# led-cube.net
KiCad netlist of a schematic drawn in EAGLE
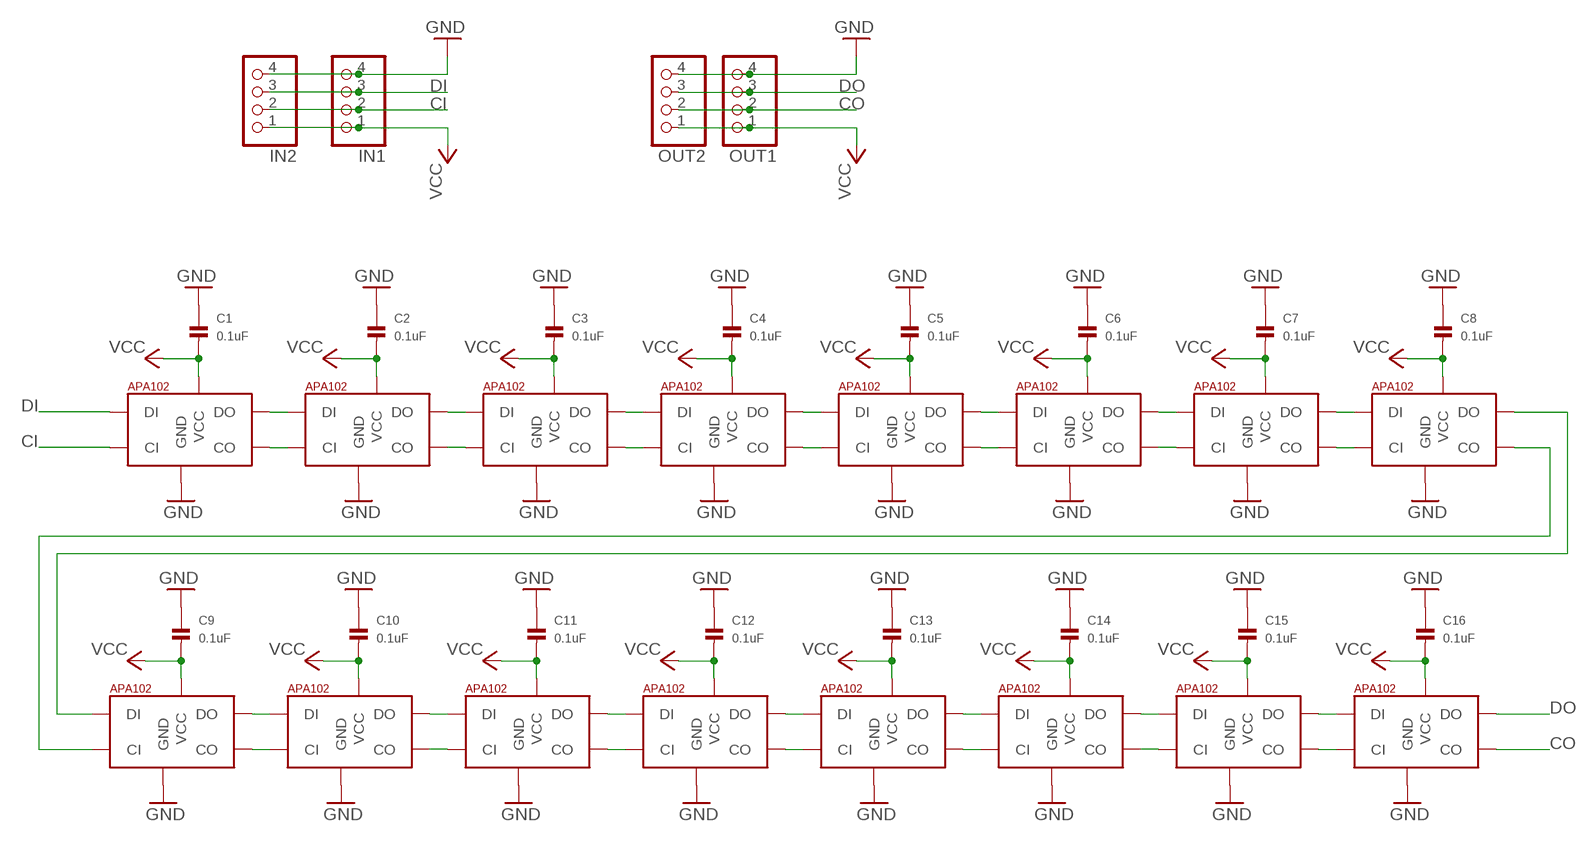
[diagram p0: schematic, sheet 1]

(export (version "E")
  (design (tool "Eeschema 10.0.6"))
  (components
    (comp (ref "C1")
      (value "0.1uF")
      (footprint "eagle-import:0603")
      (libsource (lib "eagle-import") (part "CAP_CERAMIC0603"))
    )
    (comp (ref "C2")
      (value "0.1uF")
      (footprint "eagle-import:0603")
      (libsource (lib "eagle-import") (part "CAP_CERAMIC0603"))
    )
    (comp (ref "C3")
      (value "0.1uF")
      (footprint "eagle-import:0603")
      (libsource (lib "eagle-import") (part "CAP_CERAMIC0603"))
    )
    (comp (ref "C4")
      (value "0.1uF")
      (footprint "eagle-import:0603")
      (libsource (lib "eagle-import") (part "CAP_CERAMIC0603"))
    )
    (comp (ref "C5")
      (value "0.1uF")
      (footprint "eagle-import:0603")
      (libsource (lib "eagle-import") (part "CAP_CERAMIC0603"))
    )
    (comp (ref "C6")
      (value "0.1uF")
      (footprint "eagle-import:0603")
      (libsource (lib "eagle-import") (part "CAP_CERAMIC0603"))
    )
    (comp (ref "C7")
      (value "0.1uF")
      (footprint "eagle-import:0603")
      (libsource (lib "eagle-import") (part "CAP_CERAMIC0603"))
    )
    (comp (ref "C8")
      (value "0.1uF")
      (footprint "eagle-import:0603")
      (libsource (lib "eagle-import") (part "CAP_CERAMIC0603"))
    )
    (comp (ref "C9")
      (value "0.1uF")
      (footprint "eagle-import:0603")
      (libsource (lib "eagle-import") (part "CAP_CERAMIC0603"))
    )
    (comp (ref "C10")
      (value "0.1uF")
      (footprint "eagle-import:0603")
      (libsource (lib "eagle-import") (part "CAP_CERAMIC0603"))
    )
    (comp (ref "C11")
      (value "0.1uF")
      (footprint "eagle-import:0603")
      (libsource (lib "eagle-import") (part "CAP_CERAMIC0603"))
    )
    (comp (ref "C12")
      (value "0.1uF")
      (footprint "eagle-import:0603")
      (libsource (lib "eagle-import") (part "CAP_CERAMIC0603"))
    )
    (comp (ref "C13")
      (value "0.1uF")
      (footprint "eagle-import:0603")
      (libsource (lib "eagle-import") (part "CAP_CERAMIC0603"))
    )
    (comp (ref "C14")
      (value "0.1uF")
      (footprint "eagle-import:0603")
      (libsource (lib "eagle-import") (part "CAP_CERAMIC0603"))
    )
    (comp (ref "C15")
      (value "0.1uF")
      (footprint "eagle-import:0603")
      (libsource (lib "eagle-import") (part "CAP_CERAMIC0603"))
    )
    (comp (ref "C16")
      (value "0.1uF")
      (footprint "eagle-import:0603")
      (libsource (lib "eagle-import") (part "CAP_CERAMIC0603"))
    )
    (comp (ref "IN1")
      (value "PINHD-1X4")
      (footprint "eagle-import:1X04")
      (libsource (lib "eagle-import") (part "PINHD-1X4"))
    )
    (comp (ref "IN2")
      (value "PINHD-1X4")
      (footprint "eagle-import:1X04")
      (libsource (lib "eagle-import") (part "PINHD-1X4"))
    )
    (comp (ref "OUT1")
      (value "PINHD-1X4")
      (footprint "eagle-import:1X04")
      (libsource (lib "eagle-import") (part "PINHD-1X4"))
    )
    (comp (ref "OUT2")
      (value "PINHD-1X4")
      (footprint "eagle-import:1X04")
      (libsource (lib "eagle-import") (part "PINHD-1X4"))
    )
    (comp (ref "U$1")
      (value "APA1025050")
      (footprint "eagle-import:APA102_5050")
      (libsource (lib "eagle-import") (part "APA1025050"))
    )
    (comp (ref "U$2")
      (value "APA1025050")
      (footprint "eagle-import:APA102_5050")
      (libsource (lib "eagle-import") (part "APA1025050"))
    )
    (comp (ref "U$3")
      (value "APA1025050")
      (footprint "eagle-import:APA102_5050")
      (libsource (lib "eagle-import") (part "APA1025050"))
    )
    (comp (ref "U$4")
      (value "APA1025050")
      (footprint "eagle-import:APA102_5050")
      (libsource (lib "eagle-import") (part "APA1025050"))
    )
    (comp (ref "U$5")
      (value "APA1025050")
      (footprint "eagle-import:APA102_5050")
      (libsource (lib "eagle-import") (part "APA1025050"))
    )
    (comp (ref "U$6")
      (value "APA1025050")
      (footprint "eagle-import:APA102_5050")
      (libsource (lib "eagle-import") (part "APA1025050"))
    )
    (comp (ref "U$7")
      (value "APA1025050")
      (footprint "eagle-import:APA102_5050")
      (libsource (lib "eagle-import") (part "APA1025050"))
    )
    (comp (ref "U$8")
      (value "APA1025050")
      (footprint "eagle-import:APA102_5050")
      (libsource (lib "eagle-import") (part "APA1025050"))
    )
    (comp (ref "U$9")
      (value "APA1025050")
      (footprint "eagle-import:APA102_5050")
      (libsource (lib "eagle-import") (part "APA1025050"))
    )
    (comp (ref "U$10")
      (value "APA1025050")
      (footprint "eagle-import:APA102_5050")
      (libsource (lib "eagle-import") (part "APA1025050"))
    )
    (comp (ref "U$11")
      (value "APA1025050")
      (footprint "eagle-import:APA102_5050")
      (libsource (lib "eagle-import") (part "APA1025050"))
    )
    (comp (ref "U$12")
      (value "APA1025050")
      (footprint "eagle-import:APA102_5050")
      (libsource (lib "eagle-import") (part "APA1025050"))
    )
    (comp (ref "U$13")
      (value "APA1025050")
      (footprint "eagle-import:APA102_5050")
      (libsource (lib "eagle-import") (part "APA1025050"))
    )
    (comp (ref "U$14")
      (value "APA1025050")
      (footprint "eagle-import:APA102_5050")
      (libsource (lib "eagle-import") (part "APA1025050"))
    )
    (comp (ref "U$15")
      (value "APA1025050")
      (footprint "eagle-import:APA102_5050")
      (libsource (lib "eagle-import") (part "APA1025050"))
    )
    (comp (ref "U$16")
      (value "APA1025050")
      (footprint "eagle-import:APA102_5050")
      (libsource (lib "eagle-import") (part "APA1025050"))
    )
  )
  (nets
    (net (code "1") (name "/CI") (class "Default")
      (node (ref "IN1") (pin "2") (pinfunction "2_2") (pintype "passive"))
      (node (ref "IN2") (pin "2") (pinfunction "2_2") (pintype "passive"))
      (node (ref "U$1") (pin "5") (pinfunction "CI_5") (pintype "bidirectional"))
    )
    (net (code "2") (name "/CO") (class "Default")
      (node (ref "OUT1") (pin "2") (pinfunction "2_2") (pintype "passive"))
      (node (ref "OUT2") (pin "2") (pinfunction "2_2") (pintype "passive"))
      (node (ref "U$16") (pin "2") (pinfunction "CO_2") (pintype "bidirectional"))
    )
    (net (code "3") (name "/DI") (class "Default")
      (node (ref "IN1") (pin "3") (pinfunction "3_3") (pintype "passive"))
      (node (ref "IN2") (pin "3") (pinfunction "3_3") (pintype "passive"))
      (node (ref "U$1") (pin "4") (pinfunction "DI_4") (pintype "bidirectional"))
    )
    (net (code "4") (name "/DO") (class "Default")
      (node (ref "OUT1") (pin "3") (pinfunction "3_3") (pintype "passive"))
      (node (ref "OUT2") (pin "3") (pinfunction "3_3") (pintype "passive"))
      (node (ref "U$16") (pin "3") (pinfunction "DO_3") (pintype "bidirectional"))
    )
    (net (code "5") (name "GND") (class "Default")
      (node (ref "C1") (pin "1") (pinfunction "P$1_1") (pintype "passive"))
      (node (ref "C10") (pin "1") (pinfunction "P$1_1") (pintype "passive"))
      (node (ref "C11") (pin "1") (pinfunction "P$1_1") (pintype "passive"))
      (node (ref "C12") (pin "1") (pinfunction "P$1_1") (pintype "passive"))
      (node (ref "C13") (pin "1") (pinfunction "P$1_1") (pintype "passive"))
      (node (ref "C14") (pin "1") (pinfunction "P$1_1") (pintype "passive"))
      (node (ref "C15") (pin "1") (pinfunction "P$1_1") (pintype "passive"))
      (node (ref "C16") (pin "1") (pinfunction "P$1_1") (pintype "passive"))
      (node (ref "C2") (pin "1") (pinfunction "P$1_1") (pintype "passive"))
      (node (ref "C3") (pin "1") (pinfunction "P$1_1") (pintype "passive"))
      (node (ref "C4") (pin "1") (pinfunction "P$1_1") (pintype "passive"))
      (node (ref "C5") (pin "1") (pinfunction "P$1_1") (pintype "passive"))
      (node (ref "C6") (pin "1") (pinfunction "P$1_1") (pintype "passive"))
      (node (ref "C7") (pin "1") (pinfunction "P$1_1") (pintype "passive"))
      (node (ref "C8") (pin "1") (pinfunction "P$1_1") (pintype "passive"))
      (node (ref "C9") (pin "1") (pinfunction "P$1_1") (pintype "passive"))
      (node (ref "IN1") (pin "4") (pinfunction "4_4") (pintype "passive"))
      (node (ref "IN2") (pin "4") (pinfunction "4_4") (pintype "passive"))
      (node (ref "OUT1") (pin "4") (pinfunction "4_4") (pintype "passive"))
      (node (ref "OUT2") (pin "4") (pinfunction "4_4") (pintype "passive"))
      (node (ref "U$1") (pin "6") (pinfunction "GND_6") (pintype "bidirectional"))
      (node (ref "U$10") (pin "6") (pinfunction "GND_6") (pintype "bidirectional"))
      (node (ref "U$11") (pin "6") (pinfunction "GND_6") (pintype "bidirectional"))
      (node (ref "U$12") (pin "6") (pinfunction "GND_6") (pintype "bidirectional"))
      (node (ref "U$13") (pin "6") (pinfunction "GND_6") (pintype "bidirectional"))
      (node (ref "U$14") (pin "6") (pinfunction "GND_6") (pintype "bidirectional"))
      (node (ref "U$15") (pin "6") (pinfunction "GND_6") (pintype "bidirectional"))
      (node (ref "U$16") (pin "6") (pinfunction "GND_6") (pintype "bidirectional"))
      (node (ref "U$2") (pin "6") (pinfunction "GND_6") (pintype "bidirectional"))
      (node (ref "U$3") (pin "6") (pinfunction "GND_6") (pintype "bidirectional"))
      (node (ref "U$4") (pin "6") (pinfunction "GND_6") (pintype "bidirectional"))
      (node (ref "U$5") (pin "6") (pinfunction "GND_6") (pintype "bidirectional"))
      (node (ref "U$6") (pin "6") (pinfunction "GND_6") (pintype "bidirectional"))
      (node (ref "U$7") (pin "6") (pinfunction "GND_6") (pintype "bidirectional"))
      (node (ref "U$8") (pin "6") (pinfunction "GND_6") (pintype "bidirectional"))
      (node (ref "U$9") (pin "6") (pinfunction "GND_6") (pintype "bidirectional"))
    )
    (net (code "6") (name "Net-(U$1-CO)") (class "Default")
      (node (ref "U$1") (pin "2") (pinfunction "CO_2") (pintype "bidirectional"))
      (node (ref "U$2") (pin "5") (pinfunction "CI_5") (pintype "bidirectional"))
    )
    (net (code "7") (name "Net-(U$1-DO)") (class "Default")
      (node (ref "U$1") (pin "3") (pinfunction "DO_3") (pintype "bidirectional"))
      (node (ref "U$2") (pin "4") (pinfunction "DI_4") (pintype "bidirectional"))
    )
    (net (code "8") (name "Net-(U$2-CO)") (class "Default")
      (node (ref "U$2") (pin "2") (pinfunction "CO_2") (pintype "bidirectional"))
      (node (ref "U$3") (pin "5") (pinfunction "CI_5") (pintype "bidirectional"))
    )
    (net (code "9") (name "Net-(U$2-DO)") (class "Default")
      (node (ref "U$2") (pin "3") (pinfunction "DO_3") (pintype "bidirectional"))
      (node (ref "U$3") (pin "4") (pinfunction "DI_4") (pintype "bidirectional"))
    )
    (net (code "10") (name "Net-(U$3-CO)") (class "Default")
      (node (ref "U$3") (pin "2") (pinfunction "CO_2") (pintype "bidirectional"))
      (node (ref "U$4") (pin "5") (pinfunction "CI_5") (pintype "bidirectional"))
    )
    (net (code "11") (name "Net-(U$3-DO)") (class "Default")
      (node (ref "U$3") (pin "3") (pinfunction "DO_3") (pintype "bidirectional"))
      (node (ref "U$4") (pin "4") (pinfunction "DI_4") (pintype "bidirectional"))
    )
    (net (code "12") (name "Net-(U$4-CO)") (class "Default")
      (node (ref "U$4") (pin "2") (pinfunction "CO_2") (pintype "bidirectional"))
      (node (ref "U$5") (pin "5") (pinfunction "CI_5") (pintype "bidirectional"))
    )
    (net (code "13") (name "Net-(U$4-DO)") (class "Default")
      (node (ref "U$4") (pin "3") (pinfunction "DO_3") (pintype "bidirectional"))
      (node (ref "U$5") (pin "4") (pinfunction "DI_4") (pintype "bidirectional"))
    )
    (net (code "14") (name "Net-(U$5-CO)") (class "Default")
      (node (ref "U$5") (pin "2") (pinfunction "CO_2") (pintype "bidirectional"))
      (node (ref "U$6") (pin "5") (pinfunction "CI_5") (pintype "bidirectional"))
    )
    (net (code "15") (name "Net-(U$5-DO)") (class "Default")
      (node (ref "U$5") (pin "3") (pinfunction "DO_3") (pintype "bidirectional"))
      (node (ref "U$6") (pin "4") (pinfunction "DI_4") (pintype "bidirectional"))
    )
    (net (code "16") (name "Net-(U$6-CO)") (class "Default")
      (node (ref "U$6") (pin "2") (pinfunction "CO_2") (pintype "bidirectional"))
      (node (ref "U$7") (pin "5") (pinfunction "CI_5") (pintype "bidirectional"))
    )
    (net (code "17") (name "Net-(U$6-DO)") (class "Default")
      (node (ref "U$6") (pin "3") (pinfunction "DO_3") (pintype "bidirectional"))
      (node (ref "U$7") (pin "4") (pinfunction "DI_4") (pintype "bidirectional"))
    )
    (net (code "18") (name "Net-(U$7-CO)") (class "Default")
      (node (ref "U$7") (pin "2") (pinfunction "CO_2") (pintype "bidirectional"))
      (node (ref "U$8") (pin "5") (pinfunction "CI_5") (pintype "bidirectional"))
    )
    (net (code "19") (name "Net-(U$7-DO)") (class "Default")
      (node (ref "U$7") (pin "3") (pinfunction "DO_3") (pintype "bidirectional"))
      (node (ref "U$8") (pin "4") (pinfunction "DI_4") (pintype "bidirectional"))
    )
    (net (code "20") (name "Net-(U$8-CO)") (class "Default")
      (node (ref "U$8") (pin "2") (pinfunction "CO_2") (pintype "bidirectional"))
      (node (ref "U$9") (pin "5") (pinfunction "CI_5") (pintype "bidirectional"))
    )
    (net (code "21") (name "Net-(U$8-DO)") (class "Default")
      (node (ref "U$8") (pin "3") (pinfunction "DO_3") (pintype "bidirectional"))
      (node (ref "U$9") (pin "4") (pinfunction "DI_4") (pintype "bidirectional"))
    )
    (net (code "22") (name "Net-(U$10-CI)") (class "Default")
      (node (ref "U$10") (pin "5") (pinfunction "CI_5") (pintype "bidirectional"))
      (node (ref "U$9") (pin "2") (pinfunction "CO_2") (pintype "bidirectional"))
    )
    (net (code "23") (name "Net-(U$10-CO)") (class "Default")
      (node (ref "U$10") (pin "2") (pinfunction "CO_2") (pintype "bidirectional"))
      (node (ref "U$11") (pin "5") (pinfunction "CI_5") (pintype "bidirectional"))
    )
    (net (code "24") (name "Net-(U$10-DI)") (class "Default")
      (node (ref "U$10") (pin "4") (pinfunction "DI_4") (pintype "bidirectional"))
      (node (ref "U$9") (pin "3") (pinfunction "DO_3") (pintype "bidirectional"))
    )
    (net (code "25") (name "Net-(U$10-DO)") (class "Default")
      (node (ref "U$10") (pin "3") (pinfunction "DO_3") (pintype "bidirectional"))
      (node (ref "U$11") (pin "4") (pinfunction "DI_4") (pintype "bidirectional"))
    )
    (net (code "26") (name "Net-(U$11-CO)") (class "Default")
      (node (ref "U$11") (pin "2") (pinfunction "CO_2") (pintype "bidirectional"))
      (node (ref "U$12") (pin "5") (pinfunction "CI_5") (pintype "bidirectional"))
    )
    (net (code "27") (name "Net-(U$11-DO)") (class "Default")
      (node (ref "U$11") (pin "3") (pinfunction "DO_3") (pintype "bidirectional"))
      (node (ref "U$12") (pin "4") (pinfunction "DI_4") (pintype "bidirectional"))
    )
    (net (code "28") (name "Net-(U$12-CO)") (class "Default")
      (node (ref "U$12") (pin "2") (pinfunction "CO_2") (pintype "bidirectional"))
      (node (ref "U$13") (pin "5") (pinfunction "CI_5") (pintype "bidirectional"))
    )
    (net (code "29") (name "Net-(U$12-DO)") (class "Default")
      (node (ref "U$12") (pin "3") (pinfunction "DO_3") (pintype "bidirectional"))
      (node (ref "U$13") (pin "4") (pinfunction "DI_4") (pintype "bidirectional"))
    )
    (net (code "30") (name "Net-(U$13-CO)") (class "Default")
      (node (ref "U$13") (pin "2") (pinfunction "CO_2") (pintype "bidirectional"))
      (node (ref "U$14") (pin "5") (pinfunction "CI_5") (pintype "bidirectional"))
    )
    (net (code "31") (name "Net-(U$13-DO)") (class "Default")
      (node (ref "U$13") (pin "3") (pinfunction "DO_3") (pintype "bidirectional"))
      (node (ref "U$14") (pin "4") (pinfunction "DI_4") (pintype "bidirectional"))
    )
    (net (code "32") (name "Net-(U$14-CO)") (class "Default")
      (node (ref "U$14") (pin "2") (pinfunction "CO_2") (pintype "bidirectional"))
      (node (ref "U$15") (pin "5") (pinfunction "CI_5") (pintype "bidirectional"))
    )
    (net (code "33") (name "Net-(U$14-DO)") (class "Default")
      (node (ref "U$14") (pin "3") (pinfunction "DO_3") (pintype "bidirectional"))
      (node (ref "U$15") (pin "4") (pinfunction "DI_4") (pintype "bidirectional"))
    )
    (net (code "34") (name "Net-(U$15-CO)") (class "Default")
      (node (ref "U$15") (pin "2") (pinfunction "CO_2") (pintype "bidirectional"))
      (node (ref "U$16") (pin "5") (pinfunction "CI_5") (pintype "bidirectional"))
    )
    (net (code "35") (name "Net-(U$15-DO)") (class "Default")
      (node (ref "U$15") (pin "3") (pinfunction "DO_3") (pintype "bidirectional"))
      (node (ref "U$16") (pin "4") (pinfunction "DI_4") (pintype "bidirectional"))
    )
    (net (code "36") (name "VCC") (class "Default")
      (node (ref "C1") (pin "2") (pinfunction "P$2_2") (pintype "passive"))
      (node (ref "C10") (pin "2") (pinfunction "P$2_2") (pintype "passive"))
      (node (ref "C11") (pin "2") (pinfunction "P$2_2") (pintype "passive"))
      (node (ref "C12") (pin "2") (pinfunction "P$2_2") (pintype "passive"))
      (node (ref "C13") (pin "2") (pinfunction "P$2_2") (pintype "passive"))
      (node (ref "C14") (pin "2") (pinfunction "P$2_2") (pintype "passive"))
      (node (ref "C15") (pin "2") (pinfunction "P$2_2") (pintype "passive"))
      (node (ref "C16") (pin "2") (pinfunction "P$2_2") (pintype "passive"))
      (node (ref "C2") (pin "2") (pinfunction "P$2_2") (pintype "passive"))
      (node (ref "C3") (pin "2") (pinfunction "P$2_2") (pintype "passive"))
      (node (ref "C4") (pin "2") (pinfunction "P$2_2") (pintype "passive"))
      (node (ref "C5") (pin "2") (pinfunction "P$2_2") (pintype "passive"))
      (node (ref "C6") (pin "2") (pinfunction "P$2_2") (pintype "passive"))
      (node (ref "C7") (pin "2") (pinfunction "P$2_2") (pintype "passive"))
      (node (ref "C8") (pin "2") (pinfunction "P$2_2") (pintype "passive"))
      (node (ref "C9") (pin "2") (pinfunction "P$2_2") (pintype "passive"))
      (node (ref "IN1") (pin "1") (pinfunction "1_1") (pintype "passive"))
      (node (ref "IN2") (pin "1") (pinfunction "1_1") (pintype "passive"))
      (node (ref "OUT1") (pin "1") (pinfunction "1_1") (pintype "passive"))
      (node (ref "OUT2") (pin "1") (pinfunction "1_1") (pintype "passive"))
      (node (ref "U$1") (pin "1") (pinfunction "VCC_1") (pintype "bidirectional"))
      (node (ref "U$10") (pin "1") (pinfunction "VCC_1") (pintype "bidirectional"))
      (node (ref "U$11") (pin "1") (pinfunction "VCC_1") (pintype "bidirectional"))
      (node (ref "U$12") (pin "1") (pinfunction "VCC_1") (pintype "bidirectional"))
      (node (ref "U$13") (pin "1") (pinfunction "VCC_1") (pintype "bidirectional"))
      (node (ref "U$14") (pin "1") (pinfunction "VCC_1") (pintype "bidirectional"))
      (node (ref "U$15") (pin "1") (pinfunction "VCC_1") (pintype "bidirectional"))
      (node (ref "U$16") (pin "1") (pinfunction "VCC_1") (pintype "bidirectional"))
      (node (ref "U$2") (pin "1") (pinfunction "VCC_1") (pintype "bidirectional"))
      (node (ref "U$3") (pin "1") (pinfunction "VCC_1") (pintype "bidirectional"))
      (node (ref "U$4") (pin "1") (pinfunction "VCC_1") (pintype "bidirectional"))
      (node (ref "U$5") (pin "1") (pinfunction "VCC_1") (pintype "bidirectional"))
      (node (ref "U$6") (pin "1") (pinfunction "VCC_1") (pintype "bidirectional"))
      (node (ref "U$7") (pin "1") (pinfunction "VCC_1") (pintype "bidirectional"))
      (node (ref "U$8") (pin "1") (pinfunction "VCC_1") (pintype "bidirectional"))
      (node (ref "U$9") (pin "1") (pinfunction "VCC_1") (pintype "bidirectional"))
    )
  )
)
